# CH32X315WCU-R0.net
KiCad netlist of a schematic drawn in Altium Designer
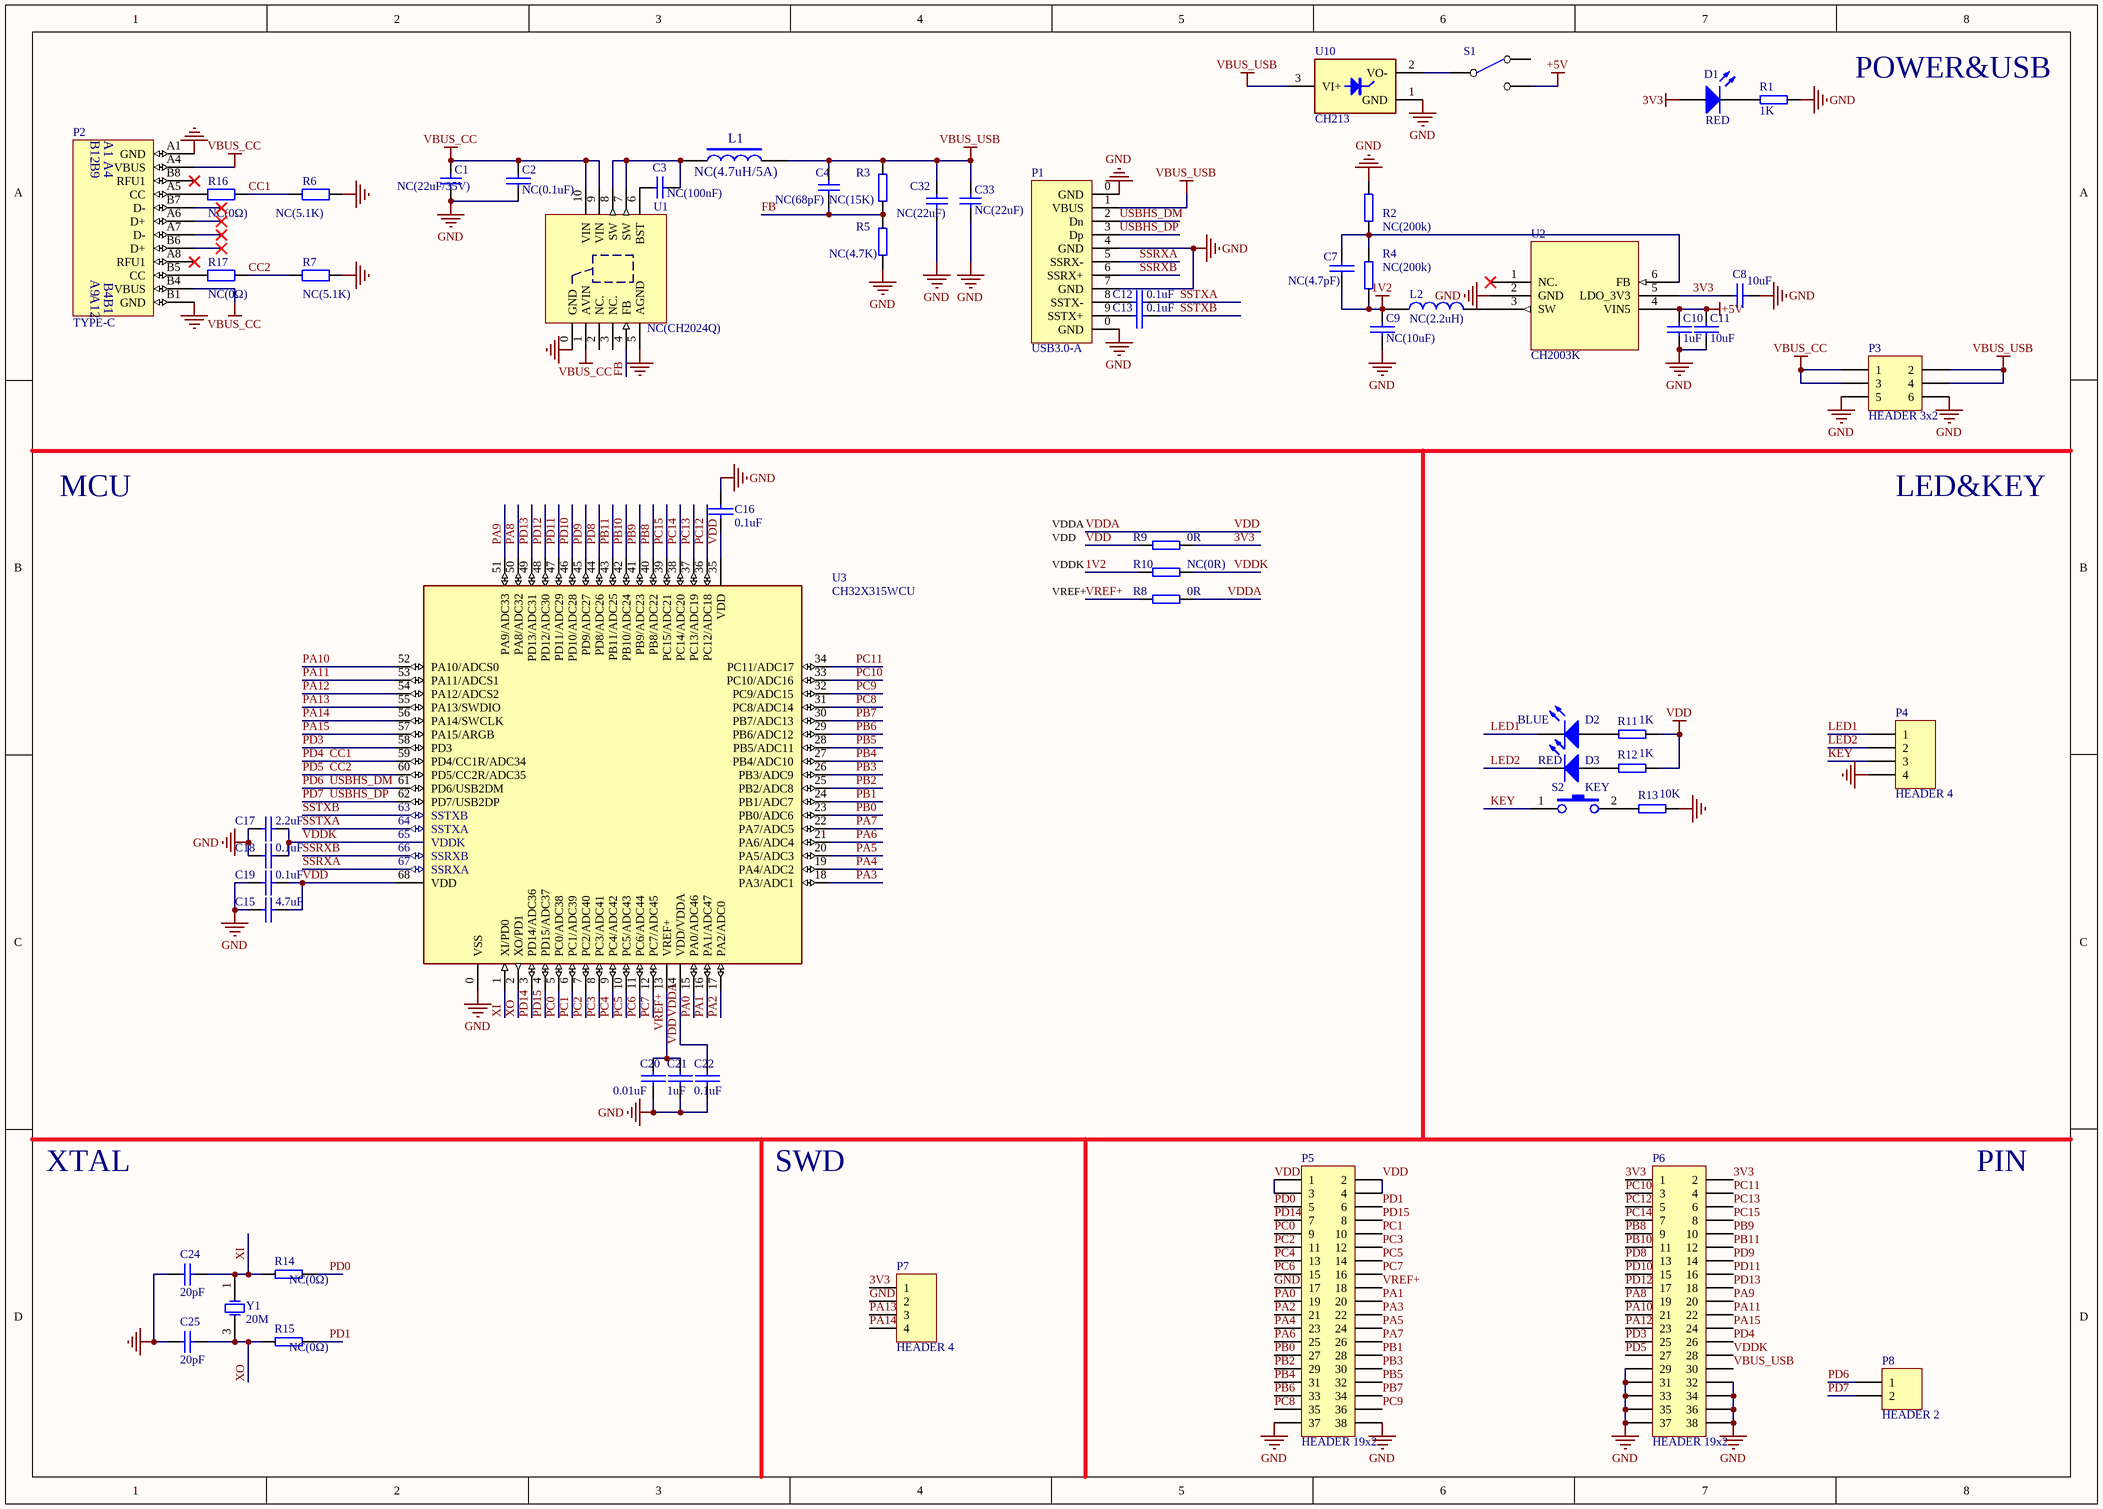
[diagram p0: CH32X315WCU-R0.SchDoc]

(export (version "E")
  (design (tool "Eeschema 10.0.6"))
  (components
    (comp (ref "C1")
      (value "NC(22uF/35V)")
      (footprint "0805_C")
      (description "贴片电容")
      (libsource (lib "Miscellaneous Devices LC") (part "0603 100nF (104) 10% 50V"))
    )
    (comp (ref "C2")
      (value "NC(0.1uF)")
      (footprint "0402_C")
      (description "Capacitor")
      (libsource (lib "") (part "CAP_1"))
    )
    (comp (ref "C3")
      (value "NC(100nF)")
      (footprint "0402_C")
      (description "贴片电容")
      (libsource (lib "Miscellaneous Devices LC") (part "0603 1uF (105) 10% 50V"))
    )
    (comp (ref "C4")
      (value "NC(68pF)")
      (footprint "0402_C")
      (description "贴片电容")
      (libsource (lib "Miscellaneous Devices LC") (part "0603 100nF (104) 10% 50V"))
    )
    (comp (ref "C7")
      (value "NC(4.7pF)")
      (footprint "0402_C")
      (description "Capacitor")
      (libsource (lib "*") (part "CAP"))
    )
    (comp (ref "C8")
      (value "10uF")
      (footprint "0603_C")
      (description "Capacitor")
      (libsource (lib "") (part "CAP_1"))
    )
    (comp (ref "C9")
      (value "NC(10uF)")
      (footprint "0603_C")
      (description "Capacitor")
      (libsource (lib "") (part "CAP_1"))
    )
    (comp (ref "C10")
      (value "1uF")
      (footprint "0402_C")
      (description "Capacitor")
      (libsource (lib "*") (part "CAP"))
    )
    (comp (ref "C11")
      (value "10uF")
      (footprint "0603_C")
      (description "Capacitor")
      (libsource (lib "") (part "CAP_1"))
    )
    (comp (ref "C12")
      (value "0.1uF")
      (footprint "0402_C")
      (description "Capacitor")
      (libsource (lib "") (part "CAP_1"))
    )
    (comp (ref "C13")
      (value "0.1uF")
      (footprint "0402_C")
      (description "Capacitor")
      (libsource (lib "") (part "CAP_1"))
    )
    (comp (ref "C15")
      (value "4.7uF")
      (footprint "0402_C")
      (description "Capacitor")
      (libsource (lib "*") (part "CAP"))
    )
    (comp (ref "C16")
      (value "0.1uF")
      (footprint "0402_C")
      (description "Capacitor")
      (libsource (lib "*") (part "CAP"))
    )
    (comp (ref "C17")
      (value "2.2uF")
      (footprint "0402_C")
      (description "Capacitor")
      (libsource (lib "*") (part "CAP"))
    )
    (comp (ref "C18")
      (value "0.1uF")
      (footprint "0402_C")
      (description "Capacitor")
      (libsource (lib "*") (part "CAP"))
    )
    (comp (ref "C19")
      (value "0.1uF")
      (footprint "0402_C")
      (description "Capacitor")
      (libsource (lib "*") (part "CAP"))
    )
    (comp (ref "C20")
      (value "0.01uF")
      (footprint "0402_C")
      (description "Capacitor")
      (libsource (lib "*") (part "CAP"))
    )
    (comp (ref "C21")
      (value "1uF")
      (footprint "0402_C")
      (description "Capacitor")
      (libsource (lib "*") (part "CAP"))
    )
    (comp (ref "C22")
      (value "0.1uF")
      (footprint "0402_C")
      (description "Capacitor")
      (libsource (lib "*") (part "CAP"))
    )
    (comp (ref "C24")
      (value "20pF")
      (footprint "0402_C")
      (description "Capacitor")
      (libsource (lib "Miscellaneous Devices") (part "Cap"))
    )
    (comp (ref "C25")
      (value "20pF")
      (footprint "0402_C")
      (description "Capacitor")
      (libsource (lib "Miscellaneous Devices") (part "Cap"))
    )
    (comp (ref "C32")
      (value "NC(22uF)")
      (footprint "0805_C")
      (description "贴片电容")
      (libsource (lib "Miscellaneous Devices LC") (part "0603 100nF (104) 10% 50V"))
    )
    (comp (ref "C33")
      (value "NC(22uF)")
      (footprint "0805_C")
      (description "贴片电容")
      (libsource (lib "Miscellaneous Devices LC") (part "0603 100nF (104) 10% 50V"))
    )
    (comp (ref "D1")
      (value "RED")
      (footprint "0603+")
      (description "Typical INFRARED GaAs LED")
      (fields (field (name "PUBLISHER") "Altium Limited"))
      (libsource (lib "*") (part "LED0"))
    )
    (comp (ref "D2")
      (value "BLUE")
      (footprint "0603+")
      (description "Typical INFRARED GaAs LED")
      (fields (field (name "PUBLISHER") "Altium Limited"))
      (libsource (lib "*") (part "LED0"))
    )
    (comp (ref "D3")
      (value "RED")
      (footprint "0603+")
      (description "Typical INFRARED GaAs LED")
      (fields (field (name "PUBLISHER") "Altium Limited"))
      (libsource (lib "*") (part "LED0"))
    )
    (comp (ref "L1")
      (value "NC(4.7uH/5A)")
      (footprint "IND-SMD_L7.0-W6.6")
      (libsource (lib "wch_sch_others") (part "INDUCTOR"))
    )
    (comp (ref "L2") (value "NC(2.2uH)") (footprint "CD32") (libsource (lib "*") (part "INDUCTOR")))
    (comp (ref "P1")
      (value "USB3.0-A")
      (footprint "USB3.0-A-Receptacle")
      (libsource (lib "wch_sch_others") (part "USB3.0-A"))
    )
    (comp (ref "P2")
      (value "TYPE-C")
      (footprint "TYPE-C-Receptacle-2.0")
      (libsource (lib "*") (part "TYPE-C1"))
    )
    (comp (ref "P3")
      (value "HEADER 3x2")
      (footprint "MYPCB:IDC6-2.54mm")
      (description "Header, 3-Pin, Dual row")
      (libsource (lib "wch_sch_others") (part "HEADER 3x2"))
    )
    (comp (ref "P4")
      (value "HEADER 4")
      (footprint "SIP4-2.54mm")
      (description "Header, 4-Pin")
      (libsource (lib "wch_sch_others") (part "HEADER 4"))
    )
    (comp (ref "P5")
      (value "HEADER 19x2")
      (footprint "MYPCB:IDC38-2.54MM")
      (description "Header, 19-Pin, Dual row")
      (libsource (lib "wch_sch_others") (part "HEADER 19x2"))
    )
    (comp (ref "P6")
      (value "HEADER 19x2")
      (footprint "MYPCB:IDC38-2.54MM")
      (description "Header, 19-Pin, Dual row")
      (libsource (lib "wch_sch_others") (part "HEADER 19x2"))
    )
    (comp (ref "P7")
      (value "HEADER 4")
      (footprint "SIP4-2.54mm")
      (description "Header, 4-Pin")
      (libsource (lib "wch_sch_others") (part "HEADER 4"))
    )
    (comp (ref "P8")
      (value "HEADER 2")
      (footprint "MYPCB:SIP2-2.54mm")
      (description "Header, 2-Pin")
      (libsource (lib "wch_sch_others") (part "HEADER 2"))
    )
    (comp (ref "R1") (value "1K") (footprint "0402") (libsource (lib "wch_sch_others") (part "RES")))
    (comp (ref "R2") (value "NC(200k)") (footprint "0402") (libsource (lib "") (part "RES_1")))
    (comp (ref "R3") (value "NC(15K)") (footprint "0402") (libsource (lib "wch_sch_others(1)") (part "RES")))
    (comp (ref "R4") (value "NC(200k)") (footprint "0402") (libsource (lib "") (part "RES_1")))
    (comp (ref "R5") (value "NC(4.7K)") (footprint "0402") (libsource (lib "wch_sch_others(1)") (part "RES")))
    (comp (ref "R6")
      (value "NC(5.1K)")
      (footprint "0402")
      (description "Resistor")
      (libsource (lib "Miscellaneous Devices") (part "Res2"))
    )
    (comp (ref "R7")
      (value "NC(5.1K)")
      (footprint "0402")
      (description "Resistor")
      (libsource (lib "Miscellaneous Devices") (part "Res2"))
    )
    (comp (ref "R8") (value "0R") (footprint "0402") (libsource (lib "*") (part "R")))
    (comp (ref "R9") (value "0R") (footprint "0402") (libsource (lib "*") (part "R")))
    (comp (ref "R10") (value "NC(0R)") (footprint "0402") (libsource (lib "*") (part "R")))
    (comp (ref "R11") (value "1K") (footprint "0402") (libsource (lib "wch_sch_others") (part "RES")))
    (comp (ref "R12") (value "1K") (footprint "0402") (libsource (lib "wch_sch_others") (part "RES")))
    (comp (ref "R13") (value "10K") (footprint "0402") (libsource (lib "wch_sch_others") (part "RES")))
    (comp (ref "R14") (value "NC(0Ω)") (footprint "0402") (libsource (lib "") (part "RES_1")))
    (comp (ref "R15") (value "NC(0Ω)") (footprint "0402") (libsource (lib "") (part "RES_1")))
    (comp (ref "R16")
      (value "NC(0Ω)")
      (footprint "0402")
      (description "Resistor")
      (libsource (lib "Miscellaneous Devices") (part "Res2"))
    )
    (comp (ref "R17")
      (value "NC(0Ω)")
      (footprint "0402")
      (description "Resistor")
      (libsource (lib "Miscellaneous Devices") (part "Res2"))
    )
    (comp (ref "S1") (value "SW SPDT") (footprint "SW1") (libsource (lib "*") (part "SW SPDT")))
    (comp (ref "S2")
      (value "KEY")
      (footprint "SMD_6.1x3.65x2.5mm-KEY")
      (libsource (lib "wch_sch_others") (part "KEY1"))
    )
    (comp (ref "U1")
      (value "NC(CH2024Q)")
      (footprint "DFN10_3X3")
      (description "Step-Down DC-DC Converter, 28V input, FB 1.2V, 3A output")
      (libsource (lib "DHXXXSCH") (part "CH2024Q"))
    )
    (comp (ref "U2")
      (value "CH2003K")
      (footprint "SOT-23-6")
      (description "Step-Down DC-DC Converter, 5V input, FB 0.6V, 800mA output, with LDO 3.3V * 200mA")
      (libsource (lib "DHXXXSCH") (part "CH2003K"))
    )
    (comp (ref "U3")
      (value "CH32X315WCU")
      (footprint "QFN68_7X7")
      (description "RISC-V FPU MCU, 480MHz, USB3.0_5Gbps, PD, HSADC")
      (libsource (lib "DHXXXSCH") (part "CH32X315WCU"))
    )
    (comp (ref "U10")
      (value "CH213")
      (footprint "SOT-23-3")
      (description "Ideal Diode 5V*1A")
      (libsource (lib "CHXXX") (part "CH213E"))
    )
    (comp (ref "Y1")
      (value "20M")
      (footprint "XT3225")
      (description "Crystal Oscillator")
      (fields (field (name "PUBLISHER") "Altium Limited"))
      (libsource (lib "Miscellaneous Devices") (part "XTAL"))
    )
  )
  (nets
    (net (code "1") (name "+5V") (class "Default")
      (node (ref "C10") (pin "2") (pinfunction "2_2") (pintype "passive"))
      (node (ref "C11") (pin "2") (pinfunction "2_2") (pintype "passive"))
      (node (ref "S1") (pin "2") (pinfunction "NC_2") (pintype "passive"))
      (node (ref "U2") (pin "4") (pinfunction "VIN5_4") (pintype "power_in"))
    )
    (net (code "3") (name "/CC1") (class "Default")
      (node (ref "P6") (pin "26") (pinfunction "26_26") (pintype "passive"))
      (node (ref "R16") (pin "2") (pinfunction "2_2") (pintype "passive"))
      (node (ref "R6") (pin "1") (pinfunction "1_1") (pintype "passive"))
      (node (ref "U3") (pin "59") (pinfunction "PD4/CC1R/ADC34_59") (pintype "bidirectional"))
    )
    (net (code "4") (name "/CC2") (class "Default")
      (node (ref "P6") (pin "27") (pinfunction "27_27") (pintype "passive"))
      (node (ref "R17") (pin "2") (pinfunction "2_2") (pintype "passive"))
      (node (ref "R7") (pin "1") (pinfunction "1_1") (pintype "passive"))
      (node (ref "U3") (pin "60") (pinfunction "PD5/CC2R/ADC35_60") (pintype "bidirectional"))
    )
    (net (code "5") (name "/FB") (class "Default")
      (node (ref "C4") (pin "2") (pinfunction "2_2") (pintype "passive"))
      (node (ref "R3") (pin "1") (pintype "passive"))
      (node (ref "R5") (pin "2") (pintype "passive"))
      (node (ref "U1") (pin "4") (pinfunction "FB_4") (pintype "input"))
    )
    (net (code "6") (name "/KEY") (class "Default")
      (node (ref "P4") (pin "3") (pinfunction "3_3") (pintype "passive"))
      (node (ref "S2") (pin "1") (pinfunction "1_1") (pintype "passive"))
    )
    (net (code "7") (name "/LED1") (class "Default")
      (node (ref "D2") (pin "2") (pinfunction "K_2") (pintype "passive"))
      (node (ref "P4") (pin "1") (pinfunction "1_1") (pintype "passive"))
    )
    (net (code "8") (name "/LED2") (class "Default")
      (node (ref "D3") (pin "2") (pinfunction "K_2") (pintype "passive"))
      (node (ref "P4") (pin "2") (pinfunction "2_2") (pintype "passive"))
    )
    (net (code "9") (name "/PA0") (class "Default")
      (node (ref "P5") (pin "19") (pinfunction "19_19") (pintype "passive"))
      (node (ref "U3") (pin "15") (pinfunction "PA0/ADC46_15") (pintype "bidirectional"))
    )
    (net (code "10") (name "/PA1") (class "Default")
      (node (ref "P5") (pin "20") (pinfunction "20_20") (pintype "passive"))
      (node (ref "U3") (pin "16") (pinfunction "PA1/ADC47_16") (pintype "bidirectional"))
    )
    (net (code "11") (name "/PA2") (class "Default")
      (node (ref "P5") (pin "21") (pinfunction "21_21") (pintype "passive"))
      (node (ref "U3") (pin "17") (pinfunction "PA2/ADC0_17") (pintype "bidirectional"))
    )
    (net (code "12") (name "/PA3") (class "Default")
      (node (ref "P5") (pin "22") (pinfunction "22_22") (pintype "passive"))
      (node (ref "U3") (pin "18") (pinfunction "PA3/ADC1_18") (pintype "bidirectional"))
    )
    (net (code "13") (name "/PA4") (class "Default")
      (node (ref "P5") (pin "23") (pinfunction "23_23") (pintype "passive"))
      (node (ref "U3") (pin "19") (pinfunction "PA4/ADC2_19") (pintype "bidirectional"))
    )
    (net (code "14") (name "/PA5") (class "Default")
      (node (ref "P5") (pin "24") (pinfunction "24_24") (pintype "passive"))
      (node (ref "U3") (pin "20") (pinfunction "PA5/ADC3_20") (pintype "bidirectional"))
    )
    (net (code "15") (name "/PA6") (class "Default")
      (node (ref "P5") (pin "25") (pinfunction "25_25") (pintype "passive"))
      (node (ref "U3") (pin "21") (pinfunction "PA6/ADC4_21") (pintype "bidirectional"))
    )
    (net (code "16") (name "/PA7") (class "Default")
      (node (ref "P5") (pin "26") (pinfunction "26_26") (pintype "passive"))
      (node (ref "U3") (pin "22") (pinfunction "PA7/ADC5_22") (pintype "bidirectional"))
    )
    (net (code "17") (name "/PA8") (class "Default")
      (node (ref "P6") (pin "19") (pinfunction "19_19") (pintype "passive"))
      (node (ref "U3") (pin "50") (pinfunction "PA8/ADC32_50") (pintype "bidirectional"))
    )
    (net (code "18") (name "/PA9") (class "Default")
      (node (ref "P6") (pin "20") (pinfunction "20_20") (pintype "passive"))
      (node (ref "U3") (pin "51") (pinfunction "PA9/ADC33_51") (pintype "bidirectional"))
    )
    (net (code "19") (name "/PA10") (class "Default")
      (node (ref "P6") (pin "21") (pinfunction "21_21") (pintype "passive"))
      (node (ref "U3") (pin "52") (pinfunction "PA10/ADCS0_52") (pintype "bidirectional"))
    )
    (net (code "20") (name "/PA11") (class "Default")
      (node (ref "P6") (pin "22") (pinfunction "22_22") (pintype "passive"))
      (node (ref "U3") (pin "53") (pinfunction "PA11/ADCS1_53") (pintype "bidirectional"))
    )
    (net (code "21") (name "/PA12") (class "Default")
      (node (ref "P6") (pin "23") (pinfunction "23_23") (pintype "passive"))
      (node (ref "U3") (pin "54") (pinfunction "PA12/ADCS2_54") (pintype "bidirectional"))
    )
    (net (code "22") (name "/PA13") (class "Default")
      (node (ref "P7") (pin "3") (pinfunction "3_3") (pintype "passive"))
      (node (ref "U3") (pin "55") (pinfunction "PA13/SWDIO_55") (pintype "bidirectional"))
    )
    (net (code "23") (name "/PA14") (class "Default")
      (node (ref "P7") (pin "4") (pinfunction "4_4") (pintype "passive"))
      (node (ref "U3") (pin "56") (pinfunction "PA14/SWCLK_56") (pintype "bidirectional"))
    )
    (net (code "24") (name "/PA15") (class "Default")
      (node (ref "P6") (pin "24") (pinfunction "24_24") (pintype "passive"))
      (node (ref "U3") (pin "57") (pinfunction "PA15/ARGB_57") (pintype "bidirectional"))
    )
    (net (code "25") (name "/PB0") (class "Default")
      (node (ref "P5") (pin "27") (pinfunction "27_27") (pintype "passive"))
      (node (ref "U3") (pin "23") (pinfunction "PB0/ADC6_23") (pintype "bidirectional"))
    )
    (net (code "26") (name "/PB1") (class "Default")
      (node (ref "P5") (pin "28") (pinfunction "28_28") (pintype "passive"))
      (node (ref "U3") (pin "24") (pinfunction "PB1/ADC7_24") (pintype "bidirectional"))
    )
    (net (code "27") (name "/PB2") (class "Default")
      (node (ref "P5") (pin "29") (pinfunction "29_29") (pintype "passive"))
      (node (ref "U3") (pin "25") (pinfunction "PB2/ADC8_25") (pintype "bidirectional"))
    )
    (net (code "28") (name "/PB3") (class "Default")
      (node (ref "P5") (pin "30") (pinfunction "30_30") (pintype "passive"))
      (node (ref "U3") (pin "26") (pinfunction "PB3/ADC9_26") (pintype "bidirectional"))
    )
    (net (code "29") (name "/PB4") (class "Default")
      (node (ref "P5") (pin "31") (pinfunction "31_31") (pintype "passive"))
      (node (ref "U3") (pin "27") (pinfunction "PB4/ADC10_27") (pintype "bidirectional"))
    )
    (net (code "30") (name "/PB5") (class "Default")
      (node (ref "P5") (pin "32") (pinfunction "32_32") (pintype "passive"))
      (node (ref "U3") (pin "28") (pinfunction "PB5/ADC11_28") (pintype "bidirectional"))
    )
    (net (code "31") (name "/PB6") (class "Default")
      (node (ref "P5") (pin "33") (pinfunction "33_33") (pintype "passive"))
      (node (ref "U3") (pin "29") (pinfunction "PB6/ADC12_29") (pintype "bidirectional"))
    )
    (net (code "32") (name "/PB7") (class "Default")
      (node (ref "P5") (pin "34") (pinfunction "34_34") (pintype "passive"))
      (node (ref "U3") (pin "30") (pinfunction "PB7/ADC13_30") (pintype "bidirectional"))
    )
    (net (code "33") (name "/PB8") (class "Default")
      (node (ref "P6") (pin "9") (pinfunction "9_9") (pintype "passive"))
      (node (ref "U3") (pin "40") (pinfunction "PB8/ADC22_40") (pintype "bidirectional"))
    )
    (net (code "34") (name "/PB9") (class "Default")
      (node (ref "P6") (pin "10") (pinfunction "10_10") (pintype "passive"))
      (node (ref "U3") (pin "41") (pinfunction "PB9/ADC23_41") (pintype "bidirectional"))
    )
    (net (code "35") (name "/PB10") (class "Default")
      (node (ref "P6") (pin "11") (pinfunction "11_11") (pintype "passive"))
      (node (ref "U3") (pin "42") (pinfunction "PB10/ADC24_42") (pintype "bidirectional"))
    )
    (net (code "36") (name "/PB11") (class "Default")
      (node (ref "P6") (pin "12") (pinfunction "12_12") (pintype "passive"))
      (node (ref "U3") (pin "43") (pinfunction "PB11/ADC25_43") (pintype "bidirectional"))
    )
    (net (code "37") (name "/PC0") (class "Default")
      (node (ref "P5") (pin "9") (pinfunction "9_9") (pintype "passive"))
      (node (ref "U3") (pin "5") (pinfunction "PC0/ADC38_5") (pintype "bidirectional"))
    )
    (net (code "38") (name "/PC1") (class "Default")
      (node (ref "P5") (pin "10") (pinfunction "10_10") (pintype "passive"))
      (node (ref "U3") (pin "6") (pinfunction "PC1/ADC39_6") (pintype "bidirectional"))
    )
    (net (code "39") (name "/PC2") (class "Default")
      (node (ref "P5") (pin "11") (pinfunction "11_11") (pintype "passive"))
      (node (ref "U3") (pin "7") (pinfunction "PC2/ADC40_7") (pintype "bidirectional"))
    )
    (net (code "40") (name "/PC3") (class "Default")
      (node (ref "P5") (pin "12") (pinfunction "12_12") (pintype "passive"))
      (node (ref "U3") (pin "8") (pinfunction "PC3/ADC41_8") (pintype "bidirectional"))
    )
    (net (code "41") (name "/PC4") (class "Default")
      (node (ref "P5") (pin "13") (pinfunction "13_13") (pintype "passive"))
      (node (ref "U3") (pin "9") (pinfunction "PC4/ADC42_9") (pintype "bidirectional"))
    )
    (net (code "42") (name "/PC5") (class "Default")
      (node (ref "P5") (pin "14") (pinfunction "14_14") (pintype "passive"))
      (node (ref "U3") (pin "10") (pinfunction "PC5/ADC43_10") (pintype "bidirectional"))
    )
    (net (code "43") (name "/PC6") (class "Default")
      (node (ref "P5") (pin "15") (pinfunction "15_15") (pintype "passive"))
      (node (ref "U3") (pin "11") (pinfunction "PC6/ADC44_11") (pintype "bidirectional"))
    )
    (net (code "44") (name "/PC7") (class "Default")
      (node (ref "P5") (pin "16") (pinfunction "16_16") (pintype "passive"))
      (node (ref "U3") (pin "12") (pinfunction "PC7/ADC45_12") (pintype "bidirectional"))
    )
    (net (code "45") (name "/PC8") (class "Default")
      (node (ref "P5") (pin "35") (pinfunction "35_35") (pintype "passive"))
      (node (ref "U3") (pin "31") (pinfunction "PC8/ADC14_31") (pintype "bidirectional"))
    )
    (net (code "46") (name "/PC9") (class "Default")
      (node (ref "P5") (pin "36") (pinfunction "36_36") (pintype "passive"))
      (node (ref "U3") (pin "32") (pinfunction "PC9/ADC15_32") (pintype "bidirectional"))
    )
    (net (code "47") (name "/PC10") (class "Default")
      (node (ref "P6") (pin "3") (pinfunction "3_3") (pintype "passive"))
      (node (ref "U3") (pin "33") (pinfunction "PC10/ADC16_33") (pintype "bidirectional"))
    )
    (net (code "48") (name "/PC11") (class "Default")
      (node (ref "P6") (pin "4") (pinfunction "4_4") (pintype "passive"))
      (node (ref "U3") (pin "34") (pinfunction "PC11/ADC17_34") (pintype "bidirectional"))
    )
    (net (code "49") (name "/PC12") (class "Default")
      (node (ref "P6") (pin "5") (pinfunction "5_5") (pintype "passive"))
      (node (ref "U3") (pin "36") (pinfunction "PC12/ADC18_36") (pintype "bidirectional"))
    )
    (net (code "50") (name "/PC13") (class "Default")
      (node (ref "P6") (pin "6") (pinfunction "6_6") (pintype "passive"))
      (node (ref "U3") (pin "37") (pinfunction "PC13/ADC19_37") (pintype "bidirectional"))
    )
    (net (code "51") (name "/PC14") (class "Default")
      (node (ref "P6") (pin "7") (pinfunction "7_7") (pintype "passive"))
      (node (ref "U3") (pin "38") (pinfunction "PC14/ADC20_38") (pintype "bidirectional"))
    )
    (net (code "52") (name "/PC15") (class "Default")
      (node (ref "P6") (pin "8") (pinfunction "8_8") (pintype "passive"))
      (node (ref "U3") (pin "39") (pinfunction "PC15/ADC21_39") (pintype "bidirectional"))
    )
    (net (code "53") (name "/PD0") (class "Default")
      (node (ref "P5") (pin "5") (pinfunction "5_5") (pintype "passive"))
      (node (ref "R14") (pin "1") (pintype "passive"))
    )
    (net (code "54") (name "/PD1") (class "Default")
      (node (ref "P5") (pin "6") (pinfunction "6_6") (pintype "passive"))
      (node (ref "R15") (pin "1") (pintype "passive"))
    )
    (net (code "55") (name "/PD3") (class "Default")
      (node (ref "P6") (pin "25") (pinfunction "25_25") (pintype "passive"))
      (node (ref "U3") (pin "58") (pinfunction "PD3_58") (pintype "bidirectional"))
    )
    (net (code "56") (name "/PD6") (class "Default")
      (node (ref "P1") (pin "2") (pinfunction "Dn_2") (pintype "passive"))
      (node (ref "P8") (pin "1") (pinfunction "1_1") (pintype "passive"))
      (node (ref "U3") (pin "61") (pinfunction "PD6/USB2DM_61") (pintype "bidirectional"))
    )
    (net (code "57") (name "/PD7") (class "Default")
      (node (ref "P1") (pin "3") (pinfunction "Dp_3") (pintype "passive"))
      (node (ref "P8") (pin "2") (pinfunction "2_2") (pintype "passive"))
      (node (ref "U3") (pin "62") (pinfunction "PD7/USB2DP_62") (pintype "bidirectional"))
    )
    (net (code "58") (name "/PD8") (class "Default")
      (node (ref "P6") (pin "13") (pinfunction "13_13") (pintype "passive"))
      (node (ref "U3") (pin "44") (pinfunction "PD8/ADC26_44") (pintype "bidirectional"))
    )
    (net (code "59") (name "/PD9") (class "Default")
      (node (ref "P6") (pin "14") (pinfunction "14_14") (pintype "passive"))
      (node (ref "U3") (pin "45") (pinfunction "PD9/ADC27_45") (pintype "bidirectional"))
    )
    (net (code "60") (name "/PD10") (class "Default")
      (node (ref "P6") (pin "15") (pinfunction "15_15") (pintype "passive"))
      (node (ref "U3") (pin "46") (pinfunction "PD10/ADC28_46") (pintype "bidirectional"))
    )
    (net (code "61") (name "/PD11") (class "Default")
      (node (ref "P6") (pin "16") (pinfunction "16_16") (pintype "passive"))
      (node (ref "U3") (pin "47") (pinfunction "PD11/ADC29_47") (pintype "bidirectional"))
    )
    (net (code "62") (name "/PD12") (class "Default")
      (node (ref "P6") (pin "17") (pinfunction "17_17") (pintype "passive"))
      (node (ref "U3") (pin "48") (pinfunction "PD12/ADC30_48") (pintype "bidirectional"))
    )
    (net (code "63") (name "/PD13") (class "Default")
      (node (ref "P6") (pin "18") (pinfunction "18_18") (pintype "passive"))
      (node (ref "U3") (pin "49") (pinfunction "PD13/ADC31_49") (pintype "bidirectional"))
    )
    (net (code "64") (name "/PD14") (class "Default")
      (node (ref "P5") (pin "7") (pinfunction "7_7") (pintype "passive"))
      (node (ref "U3") (pin "3") (pinfunction "PD14/ADC36_3") (pintype "bidirectional"))
    )
    (net (code "65") (name "/PD15") (class "Default")
      (node (ref "P5") (pin "8") (pinfunction "8_8") (pintype "passive"))
      (node (ref "U3") (pin "4") (pinfunction "PD15/ADC37_4") (pintype "bidirectional"))
    )
    (net (code "66") (name "/SSRXA") (class "Default")
      (node (ref "P1") (pin "5") (pinfunction "SSRX-_5") (pintype "passive"))
      (node (ref "U3") (pin "67") (pinfunction "SSRXA_67") (pintype "bidirectional"))
    )
    (net (code "67") (name "/SSRXB") (class "Default")
      (node (ref "P1") (pin "6") (pinfunction "SSRX+_6") (pintype "passive"))
      (node (ref "U3") (pin "66") (pinfunction "SSRXB_66") (pintype "bidirectional"))
    )
    (net (code "68") (name "/SSTXA") (class "Default")
      (node (ref "C12") (pin "2") (pinfunction "2_2") (pintype "passive"))
      (node (ref "U3") (pin "64") (pinfunction "SSTXA_64") (pintype "bidirectional"))
    )
    (net (code "69") (name "/SSTXB") (class "Default")
      (node (ref "C13") (pin "2") (pinfunction "2_2") (pintype "passive"))
      (node (ref "U3") (pin "63") (pinfunction "SSTXB_63") (pintype "bidirectional"))
    )
    (net (code "70") (name "/VDDK") (class "Default")
      (node (ref "C17") (pin "1") (pinfunction "1_1") (pintype "passive"))
      (node (ref "C18") (pin "1") (pinfunction "1_1") (pintype "passive"))
      (node (ref "P6") (pin "28") (pinfunction "28_28") (pintype "passive"))
      (node (ref "R10") (pin "1") (pinfunction "1_1") (pintype "passive"))
      (node (ref "U3") (pin "65") (pinfunction "VDDK_65") (pintype "power_in"))
    )
    (net (code "71") (name "/VREF+") (class "Default")
      (node (ref "C20") (pin "1") (pinfunction "1_1") (pintype "passive"))
      (node (ref "C21") (pin "1") (pinfunction "1_1") (pintype "passive"))
      (node (ref "P5") (pin "18") (pinfunction "18_18") (pintype "passive"))
      (node (ref "R8") (pin "2") (pinfunction "2_2") (pintype "passive"))
      (node (ref "U3") (pin "13") (pinfunction "VREF+_13") (pintype "power_in"))
    )
    (net (code "72") (name "/XI") (class "Default")
      (node (ref "C24") (pin "1") (pinfunction "1_1") (pintype "passive"))
      (node (ref "R14") (pin "2") (pintype "passive"))
      (node (ref "U3") (pin "1") (pinfunction "XI/PD0_1") (pintype "input"))
      (node (ref "Y1") (pin "1") (pinfunction "OSC1_1") (pintype "passive"))
    )
    (net (code "73") (name "/XO") (class "Default")
      (node (ref "C25") (pin "1") (pinfunction "1_1") (pintype "passive"))
      (node (ref "R15") (pin "2") (pintype "passive"))
      (node (ref "U3") (pin "2") (pinfunction "XO/PD1_2") (pintype "output"))
      (node (ref "Y1") (pin "3") (pinfunction "OSC2_3") (pintype "passive"))
    )
    (net (code "74") (name "1V2") (class "Default")
      (node (ref "C7") (pin "1") (pinfunction "1_1") (pintype "passive"))
      (node (ref "C9") (pin "2") (pinfunction "2_2") (pintype "passive"))
      (node (ref "L2") (pin "2") (pinfunction "2_2") (pintype "passive"))
      (node (ref "R10") (pin "2") (pinfunction "2_2") (pintype "passive"))
      (node (ref "R4") (pin "1") (pintype "passive"))
    )
    (net (code "75") (name "3V3") (class "Default")
      (node (ref "C8") (pin "2") (pinfunction "2_2") (pintype "passive"))
      (node (ref "D1") (pin "1") (pinfunction "A_1") (pintype "passive"))
      (node (ref "P6") (pin "1") (pinfunction "1_1") (pintype "passive"))
      (node (ref "P6") (pin "2") (pinfunction "2_2") (pintype "passive"))
      (node (ref "P7") (pin "1") (pinfunction "1_1") (pintype "passive"))
      (node (ref "R9") (pin "1") (pinfunction "1_1") (pintype "passive"))
      (node (ref "U2") (pin "5") (pinfunction "LDO_3V3_5") (pintype "power_in"))
    )
    (net (code "76") (name "GND") (class "Default")
      (node (ref "C1") (pin "1") (pinfunction "1_1") (pintype "passive"))
      (node (ref "C10") (pin "1") (pinfunction "1_1") (pintype "passive"))
      (node (ref "C11") (pin "1") (pinfunction "1_1") (pintype "passive"))
      (node (ref "C15") (pin "2") (pinfunction "2_2") (pintype "passive"))
      (node (ref "C16") (pin "1") (pinfunction "1_1") (pintype "passive"))
      (node (ref "C17") (pin "2") (pinfunction "2_2") (pintype "passive"))
      (node (ref "C18") (pin "2") (pinfunction "2_2") (pintype "passive"))
      (node (ref "C19") (pin "2") (pinfunction "2_2") (pintype "passive"))
      (node (ref "C2") (pin "1") (pinfunction "1_1") (pintype "passive"))
      (node (ref "C20") (pin "2") (pinfunction "2_2") (pintype "passive"))
      (node (ref "C21") (pin "2") (pinfunction "2_2") (pintype "passive"))
      (node (ref "C22") (pin "2") (pinfunction "2_2") (pintype "passive"))
      (node (ref "C24") (pin "2") (pinfunction "2_2") (pintype "passive"))
      (node (ref "C25") (pin "2") (pinfunction "2_2") (pintype "passive"))
      (node (ref "C32") (pin "1") (pinfunction "1_1") (pintype "passive"))
      (node (ref "C33") (pin "1") (pinfunction "1_1") (pintype "passive"))
      (node (ref "C8") (pin "1") (pinfunction "1_1") (pintype "passive"))
      (node (ref "C9") (pin "1") (pinfunction "1_1") (pintype "passive"))
      (node (ref "P1") (pin "0") (pinfunction "GND_0") (pintype "passive"))
      (node (ref "P1") (pin "4") (pinfunction "GND_4") (pintype "passive"))
      (node (ref "P1") (pin "7") (pinfunction "GND_7") (pintype "passive"))
      (node (ref "P2") (pin "A1") (pinfunction "GND_A1") (pintype "bidirectional"))
      (node (ref "P2") (pin "B1") (pinfunction "GND_B1") (pintype "bidirectional"))
      (node (ref "P3") (pin "5") (pinfunction "5_5") (pintype "passive"))
      (node (ref "P3") (pin "6") (pinfunction "6_6") (pintype "passive"))
      (node (ref "P4") (pin "4") (pinfunction "4_4") (pintype "passive"))
      (node (ref "P5") (pin "17") (pinfunction "17_17") (pintype "passive"))
      (node (ref "P5") (pin "37") (pinfunction "37_37") (pintype "passive"))
      (node (ref "P5") (pin "38") (pinfunction "38_38") (pintype "passive"))
      (node (ref "P6") (pin "29") (pinfunction "29_29") (pintype "passive"))
      (node (ref "P6") (pin "31") (pinfunction "31_31") (pintype "passive"))
      (node (ref "P6") (pin "32") (pinfunction "32_32") (pintype "passive"))
      (node (ref "P6") (pin "33") (pinfunction "33_33") (pintype "passive"))
      (node (ref "P6") (pin "34") (pinfunction "34_34") (pintype "passive"))
      (node (ref "P6") (pin "35") (pinfunction "35_35") (pintype "passive"))
      (node (ref "P6") (pin "36") (pinfunction "36_36") (pintype "passive"))
      (node (ref "P6") (pin "37") (pinfunction "37_37") (pintype "passive"))
      (node (ref "P6") (pin "38") (pinfunction "38_38") (pintype "passive"))
      (node (ref "P7") (pin "2") (pinfunction "2_2") (pintype "passive"))
      (node (ref "R1") (pin "2") (pintype "passive"))
      (node (ref "R13") (pin "1") (pintype "passive"))
      (node (ref "R2") (pin "2") (pintype "passive"))
      (node (ref "R5") (pin "1") (pintype "passive"))
      (node (ref "R6") (pin "2") (pinfunction "2_2") (pintype "passive"))
      (node (ref "R7") (pin "2") (pinfunction "2_2") (pintype "passive"))
      (node (ref "U1") (pin "0") (pinfunction "GND_0") (pintype "power_in"))
      (node (ref "U1") (pin "5") (pinfunction "AGND_5") (pintype "power_in"))
      (node (ref "U10") (pin "1") (pinfunction "GND_1") (pintype "power_in"))
      (node (ref "U2") (pin "2") (pinfunction "GND_2") (pintype "power_in"))
      (node (ref "U3") (pin "0") (pinfunction "VSS_0") (pintype "power_in"))
    )
    (net (code "77") (name "Net-(C3-Pad2)") (class "Default")
      (node (ref "C3") (pin "2") (pinfunction "2_2") (pintype "passive"))
      (node (ref "L1") (pin "1") (pinfunction "1_1") (pintype "passive"))
      (node (ref "U1") (pin "7") (pinfunction "SW_7") (pintype "output"))
      (node (ref "U1") (pin "8") (pinfunction "SW_8") (pintype "output"))
    )
    (net (code "78") (name "Net-(D1-K)") (class "Default")
      (node (ref "D1") (pin "2") (pinfunction "K_2") (pintype "passive"))
      (node (ref "R1") (pin "1") (pintype "passive"))
    )
    (net (code "79") (name "Net-(D2-A)") (class "Default")
      (node (ref "D2") (pin "1") (pinfunction "A_1") (pintype "passive"))
      (node (ref "R11") (pin "2") (pintype "passive"))
    )
    (net (code "80") (name "Net-(D3-A)") (class "Default")
      (node (ref "D3") (pin "1") (pinfunction "A_1") (pintype "passive"))
      (node (ref "R12") (pin "2") (pintype "passive"))
    )
    (net (code "81") (name "Net-(P1-SSTX+)") (class "Default")
      (node (ref "C13") (pin "1") (pinfunction "1_1") (pintype "passive"))
      (node (ref "P1") (pin "9") (pinfunction "SSTX+_9") (pintype "passive"))
    )
    (net (code "82") (name "Net-(P1-SSTX-)") (class "Default")
      (node (ref "C12") (pin "1") (pinfunction "1_1") (pintype "passive"))
      (node (ref "P1") (pin "8") (pinfunction "SSTX-_8") (pintype "passive"))
    )
    (net (code "83") (name "Net-(P2-CC-PadA5)") (class "Default")
      (node (ref "P2") (pin "A5") (pinfunction "CC_A5") (pintype "bidirectional"))
      (node (ref "R16") (pin "1") (pinfunction "1_1") (pintype "passive"))
    )
    (net (code "84") (name "Net-(P2-CC-PadB5)") (class "Default")
      (node (ref "P2") (pin "B5") (pinfunction "CC_B5") (pintype "bidirectional"))
      (node (ref "R17") (pin "1") (pinfunction "1_1") (pintype "passive"))
    )
    (net (code "85") (name "Net-(R13-Pad2)") (class "Default")
      (node (ref "R13") (pin "2") (pintype "passive"))
      (node (ref "S2") (pin "2") (pinfunction "2_2") (pintype "passive"))
    )
    (net (code "86") (name "Net-(S1-COMMON)") (class "Default")
      (node (ref "S1") (pin "1") (pinfunction "COMMON_1") (pintype "passive"))
      (node (ref "U10") (pin "2") (pinfunction "VO-_2") (pintype "power_in"))
    )
    (net (code "87") (name "Net-(U1-BST)") (class "Default")
      (node (ref "C3") (pin "1") (pinfunction "1_1") (pintype "passive"))
      (node (ref "U1") (pin "6") (pinfunction "BST_6") (pintype "power_in"))
    )
    (net (code "88") (name "Net-(U2-FB)") (class "Default")
      (node (ref "C7") (pin "2") (pinfunction "2_2") (pintype "passive"))
      (node (ref "R2") (pin "1") (pintype "passive"))
      (node (ref "R4") (pin "2") (pintype "passive"))
      (node (ref "U2") (pin "6") (pinfunction "FB_6") (pintype "input"))
    )
    (net (code "89") (name "Net-(U2-SW)") (class "Default")
      (node (ref "L2") (pin "1") (pinfunction "1_1") (pintype "passive"))
      (node (ref "U2") (pin "3") (pinfunction "SW_3") (pintype "output"))
    )
    (net (code "90") (name "VBUS_CC") (class "Default")
      (node (ref "C1") (pin "2") (pinfunction "2_2") (pintype "passive"))
      (node (ref "C2") (pin "2") (pinfunction "2_2") (pintype "passive"))
      (node (ref "P2") (pin "A4") (pinfunction "VBUS_A4") (pintype "bidirectional"))
      (node (ref "P2") (pin "B4") (pinfunction "VBUS_B4") (pintype "bidirectional"))
      (node (ref "P3") (pin "1") (pinfunction "1_1") (pintype "passive"))
      (node (ref "P3") (pin "3") (pinfunction "3_3") (pintype "passive"))
      (node (ref "U1") (pin "1") (pinfunction "AVIN_1") (pintype "power_in"))
      (node (ref "U1") (pin "10") (pinfunction "VIN_10") (pintype "power_in"))
      (node (ref "U1") (pin "9") (pinfunction "VIN_9") (pintype "power_in"))
    )
    (net (code "91") (name "VBUS_USB") (class "Default")
      (node (ref "C32") (pin "2") (pinfunction "2_2") (pintype "passive"))
      (node (ref "C33") (pin "2") (pinfunction "2_2") (pintype "passive"))
      (node (ref "C4") (pin "1") (pinfunction "1_1") (pintype "passive"))
      (node (ref "L1") (pin "2") (pinfunction "2_2") (pintype "passive"))
      (node (ref "P1") (pin "1") (pinfunction "VBUS_1") (pintype "passive"))
      (node (ref "P3") (pin "2") (pinfunction "2_2") (pintype "passive"))
      (node (ref "P3") (pin "4") (pinfunction "4_4") (pintype "passive"))
      (node (ref "P6") (pin "30") (pinfunction "30_30") (pintype "passive"))
      (node (ref "R3") (pin "2") (pintype "passive"))
      (node (ref "U10") (pin "3") (pinfunction "VI+_3") (pintype "power_in"))
    )
    (net (code "92") (name "VDD") (class "Default")
      (node (ref "C15") (pin "1") (pinfunction "1_1") (pintype "passive"))
      (node (ref "C16") (pin "2") (pinfunction "2_2") (pintype "passive"))
      (node (ref "C19") (pin "1") (pinfunction "1_1") (pintype "passive"))
      (node (ref "C22") (pin "1") (pinfunction "1_1") (pintype "passive"))
      (node (ref "P5") (pin "1") (pinfunction "1_1") (pintype "passive"))
      (node (ref "P5") (pin "2") (pinfunction "2_2") (pintype "passive"))
      (node (ref "P5") (pin "3") (pinfunction "3_3") (pintype "passive"))
      (node (ref "P5") (pin "4") (pinfunction "4_4") (pintype "passive"))
      (node (ref "R11") (pin "1") (pintype "passive"))
      (node (ref "R12") (pin "1") (pintype "passive"))
      (node (ref "R8") (pin "1") (pinfunction "1_1") (pintype "passive"))
      (node (ref "R9") (pin "2") (pinfunction "2_2") (pintype "passive"))
      (node (ref "U3") (pin "14") (pinfunction "VDD/VDDA_14") (pintype "power_in"))
      (node (ref "U3") (pin "35") (pinfunction "VDD_35") (pintype "power_in"))
      (node (ref "U3") (pin "68") (pinfunction "VDD_68") (pintype "power_in"))
    )
    (net (code "93") (name "unconnected-(P2-D+-PadA6)") (class "Default")
      (node (ref "P2") (pin "A6") (pinfunction "D+_A6") (pintype "bidirectional+no_connect"))
    )
    (net (code "94") (name "unconnected-(P2-D+-PadB6)") (class "Default")
      (node (ref "P2") (pin "B6") (pinfunction "D+_B6") (pintype "bidirectional+no_connect"))
    )
    (net (code "95") (name "unconnected-(P2-D--PadA7)") (class "Default")
      (node (ref "P2") (pin "A7") (pinfunction "D-_A7") (pintype "bidirectional+no_connect"))
    )
    (net (code "96") (name "unconnected-(P2-D--PadB7)") (class "Default")
      (node (ref "P2") (pin "B7") (pinfunction "D-_B7") (pintype "bidirectional+no_connect"))
    )
    (net (code "97") (name "unconnected-(P2-RFU1-PadA8)") (class "Default")
      (node (ref "P2") (pin "A8") (pinfunction "RFU1_A8") (pintype "bidirectional+no_connect"))
    )
    (net (code "98") (name "unconnected-(P2-RFU1-PadB8)") (class "Default")
      (node (ref "P2") (pin "B8") (pinfunction "RFU1_B8") (pintype "bidirectional+no_connect"))
    )
    (net (code "99") (name "unconnected-(S1-NO-Pad3)") (class "Default")
      (node (ref "S1") (pin "3") (pinfunction "NO_3") (pintype "passive"))
    )
    (net (code "100") (name "unconnected-(U1-NC.-Pad2)") (class "Default")
      (node (ref "U1") (pin "2") (pinfunction "NC._2") (pintype "passive"))
    )
    (net (code "101") (name "unconnected-(U1-NC.-Pad3)") (class "Default")
      (node (ref "U1") (pin "3") (pinfunction "NC._3") (pintype "passive"))
    )
    (net (code "102") (name "unconnected-(U2-NC.-Pad1)") (class "Default")
      (node (ref "U2") (pin "1") (pinfunction "NC._1") (pintype "passive+no_connect"))
    )
  )
)
